# Eric_Dog_Tag_PCB.net
KiCad netlist of a schematic drawn in Altium Designer
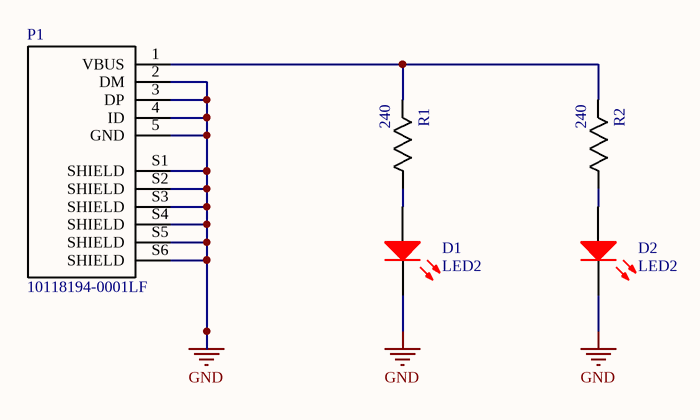
[diagram p0: Eric Dog Tag PCB.SchDoc]

(export (version "E")
  (design (tool "Eeschema 10.0.6"))
  (components
    (comp (ref "D1")
      (value "LED2")
      (footprint "3.2X1.6X1.1")
      (description "Typical RED, GREEN, YELLOW, AMBER GaAs LED")
      (libsource (lib "AltiumLibraries") (part "LED RED SMD"))
    )
    (comp (ref "D2")
      (value "LED2")
      (footprint "3.2X1.6X1.1")
      (description "Typical RED, GREEN, YELLOW, AMBER GaAs LED")
      (libsource (lib "AltiumLibraries") (part "LED RED SMD"))
    )
    (comp (ref "P1")
      (value "10118194-0001LF")
      (footprint "USB Micro B Receptacle")
      (description "USB - micro B USB 2.0 Receptacle Connector 5 Position Surface Mount, Right Angle; Through Hole")
      (fields (field (name "MF") "Amphenol ICC (FCI)"))
      (libsource (lib "AltiumLibraries") (part "USB Micro B Receptacle"))
    )
    (comp (ref "R1")
      (value "240")
      (footprint "0805")
      (description "RES SMD 240 OHM 5% 1/8W 0805")
      (fields (field (name "TOLERANCE") "5%"))
      (libsource (lib "") (part "RES 240.0 1/8W_1"))
    )
    (comp (ref "R2")
      (value "240")
      (footprint "0805")
      (description "RES SMD 240 OHM 5% 1/8W 0805")
      (fields (field (name "TOLERANCE") "5%"))
      (libsource (lib "AltiumLibraries") (part "RES 240.0 1/8W"))
    )
  )
  (nets
    (net (code "1") (name "GND") (class "Default")
      (node (ref "D1") (pin "2") (pinfunction "K_2") (pintype "passive"))
      (node (ref "D2") (pin "2") (pinfunction "K_2") (pintype "passive"))
      (node (ref "P1") (pin "2") (pinfunction "DM_2") (pintype "passive"))
      (node (ref "P1") (pin "3") (pinfunction "DP_3") (pintype "passive"))
      (node (ref "P1") (pin "4") (pinfunction "ID_4") (pintype "passive"))
      (node (ref "P1") (pin "5") (pinfunction "GND_5") (pintype "passive"))
      (node (ref "P1") (pin "S1") (pinfunction "SHIELD_S1") (pintype "passive"))
      (node (ref "P1") (pin "S2") (pinfunction "SHIELD_S2") (pintype "passive"))
      (node (ref "P1") (pin "S3") (pinfunction "SHIELD_S3") (pintype "passive"))
      (node (ref "P1") (pin "S4") (pinfunction "SHIELD_S4") (pintype "passive"))
      (node (ref "P1") (pin "S5") (pinfunction "SHIELD_S5") (pintype "passive"))
      (node (ref "P1") (pin "S6") (pinfunction "SHIELD_S6") (pintype "passive"))
    )
    (net (code "2") (name "Net-(D1-A)") (class "Default")
      (node (ref "D1") (pin "1") (pinfunction "A_1") (pintype "passive"))
      (node (ref "R1") (pin "1") (pinfunction "R1_1") (pintype "passive"))
    )
    (net (code "3") (name "Net-(D2-A)") (class "Default")
      (node (ref "D2") (pin "1") (pinfunction "A_1") (pintype "passive"))
      (node (ref "R2") (pin "1") (pinfunction "R1_1") (pintype "passive"))
    )
    (net (code "4") (name "Net-(P1-VBUS)") (class "Default")
      (node (ref "P1") (pin "1") (pinfunction "VBUS_1") (pintype "passive"))
      (node (ref "R1") (pin "2") (pinfunction "R2_2") (pintype "passive"))
      (node (ref "R2") (pin "2") (pinfunction "R2_2") (pintype "passive"))
    )
  )
)
